# NHD-C12832A-Breakout.net
KiCad netlist of a schematic drawn in EAGLE
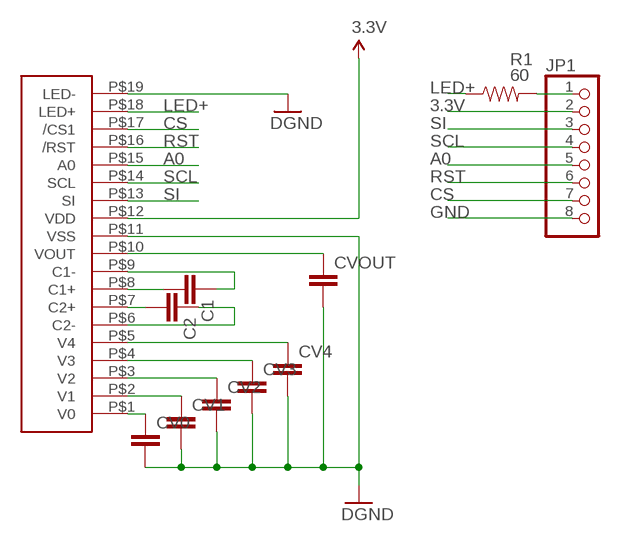
[diagram p0: schematic, sheet 1]

(export (version "E")
  (design (tool "Eeschema 10.0.6"))
  (components
    (comp (ref "C1")
      (value "C-EUC0805")
      (footprint "eagle-import:C0805")
      (libsource (lib "eagle-import") (part "C-EUC0805"))
    )
    (comp (ref "C2")
      (value "C-EUC0805")
      (footprint "eagle-import:C0805")
      (libsource (lib "eagle-import") (part "C-EUC0805"))
    )
    (comp (ref "CV0")
      (value "C-EUC0805")
      (footprint "eagle-import:C0805")
      (libsource (lib "eagle-import") (part "C-EUC0805"))
    )
    (comp (ref "CV1")
      (value "C-EUC0805")
      (footprint "eagle-import:C0805")
      (libsource (lib "eagle-import") (part "C-EUC0805"))
    )
    (comp (ref "CV2")
      (value "C-EUC0805")
      (footprint "eagle-import:C0805")
      (libsource (lib "eagle-import") (part "C-EUC0805"))
    )
    (comp (ref "CV3")
      (value "C-EUC0805")
      (footprint "eagle-import:C0805")
      (libsource (lib "eagle-import") (part "C-EUC0805"))
    )
    (comp (ref "CV4")
      (value "C-EUC0805")
      (footprint "eagle-import:C0805")
      (libsource (lib "eagle-import") (part "C-EUC0805"))
    )
    (comp (ref "CVOUT")
      (value "C-EUC0805")
      (footprint "eagle-import:C0805")
      (libsource (lib "eagle-import") (part "C-EUC0805"))
    )
    (comp (ref "JP1")
      (value "PINHD-1X8")
      (footprint "eagle-import:1X08")
      (libsource (lib "eagle-import") (part "PINHD-1X8"))
    )
    (comp (ref "R1")
      (value "60")
      (footprint "eagle-import:0805")
      (libsource (lib "eagle-import") (part "RESISTOR0805-RES"))
    )
    (comp (ref "U$1")
      (value "NHD-C12832A")
      (footprint "eagle-import:NHD-C12832A-PACK")
      (libsource (lib "eagle-import") (part "NHD-C12832A"))
    )
  )
  (nets
    (net (code "1") (name "/A0") (class "Default")
      (node (ref "JP1") (pin "5") (pinfunction "5_5") (pintype "passive"))
      (node (ref "U$1") (pin "P$15") (pinfunction "A0_P$15") (pintype "bidirectional"))
    )
    (net (code "2") (name "/CS") (class "Default")
      (node (ref "JP1") (pin "7") (pinfunction "7_7") (pintype "passive"))
      (node (ref "U$1") (pin "P$17") (pinfunction "/CS1_P$17") (pintype "bidirectional"))
    )
    (net (code "3") (name "/LED+") (class "Default")
      (node (ref "R1") (pin "1") (pinfunction "1_1") (pintype "passive"))
      (node (ref "U$1") (pin "P$18") (pinfunction "LED+_P$18") (pintype "bidirectional"))
    )
    (net (code "4") (name "/RST") (class "Default")
      (node (ref "JP1") (pin "6") (pinfunction "6_6") (pintype "passive"))
      (node (ref "U$1") (pin "P$16") (pinfunction "/RST_P$16") (pintype "bidirectional"))
    )
    (net (code "5") (name "/SCL") (class "Default")
      (node (ref "JP1") (pin "4") (pinfunction "4_4") (pintype "passive"))
      (node (ref "U$1") (pin "P$14") (pinfunction "SCL_P$14") (pintype "bidirectional"))
    )
    (net (code "6") (name "/SI") (class "Default")
      (node (ref "JP1") (pin "3") (pinfunction "3_3") (pintype "passive"))
      (node (ref "U$1") (pin "P$13") (pinfunction "SI_P$13") (pintype "bidirectional"))
    )
    (net (code "7") (name "3.3V") (class "Default")
      (node (ref "JP1") (pin "2") (pinfunction "2_2") (pintype "passive"))
      (node (ref "U$1") (pin "P$12") (pinfunction "VDD_P$12") (pintype "bidirectional"))
    )
    (net (code "8") (name "DGND") (class "Default")
      (node (ref "CV0") (pin "2") (pinfunction "2_2") (pintype "passive"))
      (node (ref "CV1") (pin "2") (pinfunction "2_2") (pintype "passive"))
      (node (ref "CV2") (pin "2") (pinfunction "2_2") (pintype "passive"))
      (node (ref "CV3") (pin "2") (pinfunction "2_2") (pintype "passive"))
      (node (ref "CV4") (pin "2") (pinfunction "2_2") (pintype "passive"))
      (node (ref "CVOUT") (pin "2") (pinfunction "2_2") (pintype "passive"))
      (node (ref "JP1") (pin "8") (pinfunction "8_8") (pintype "passive"))
      (node (ref "U$1") (pin "P$11") (pinfunction "VSS_P$11") (pintype "bidirectional"))
      (node (ref "U$1") (pin "P$19") (pinfunction "LED-_P$19") (pintype "bidirectional"))
    )
    (net (code "9") (name "Net-(JP1-Pad1)") (class "Default")
      (node (ref "JP1") (pin "1") (pinfunction "1_1") (pintype "passive"))
      (node (ref "R1") (pin "2") (pinfunction "2_2") (pintype "passive"))
    )
    (net (code "10") (name "Net-(U$1-C1+)") (class "Default")
      (node (ref "C1") (pin "2") (pinfunction "2_2") (pintype "passive"))
      (node (ref "U$1") (pin "P$8") (pinfunction "C1+_P$8") (pintype "bidirectional"))
    )
    (net (code "11") (name "Net-(U$1-C1-)") (class "Default")
      (node (ref "C1") (pin "1") (pinfunction "1_1") (pintype "passive"))
      (node (ref "U$1") (pin "P$9") (pinfunction "C1-_P$9") (pintype "bidirectional"))
    )
    (net (code "12") (name "Net-(U$1-C2+)") (class "Default")
      (node (ref "C2") (pin "2") (pinfunction "2_2") (pintype "passive"))
      (node (ref "U$1") (pin "P$7") (pinfunction "C2+_P$7") (pintype "bidirectional"))
    )
    (net (code "13") (name "Net-(U$1-C2-)") (class "Default")
      (node (ref "C2") (pin "1") (pinfunction "1_1") (pintype "passive"))
      (node (ref "U$1") (pin "P$6") (pinfunction "C2-_P$6") (pintype "bidirectional"))
    )
    (net (code "14") (name "Net-(U$1-V0)") (class "Default")
      (node (ref "CV0") (pin "1") (pinfunction "1_1") (pintype "passive"))
      (node (ref "U$1") (pin "P$1") (pinfunction "V0_P$1") (pintype "bidirectional"))
    )
    (net (code "15") (name "Net-(U$1-V1)") (class "Default")
      (node (ref "CV1") (pin "1") (pinfunction "1_1") (pintype "passive"))
      (node (ref "U$1") (pin "P$2") (pinfunction "V1_P$2") (pintype "bidirectional"))
    )
    (net (code "16") (name "Net-(U$1-V2)") (class "Default")
      (node (ref "CV2") (pin "1") (pinfunction "1_1") (pintype "passive"))
      (node (ref "U$1") (pin "P$3") (pinfunction "V2_P$3") (pintype "bidirectional"))
    )
    (net (code "17") (name "Net-(U$1-V3)") (class "Default")
      (node (ref "CV3") (pin "1") (pinfunction "1_1") (pintype "passive"))
      (node (ref "U$1") (pin "P$4") (pinfunction "V3_P$4") (pintype "bidirectional"))
    )
    (net (code "18") (name "Net-(U$1-V4)") (class "Default")
      (node (ref "CV4") (pin "1") (pinfunction "1_1") (pintype "passive"))
      (node (ref "U$1") (pin "P$5") (pinfunction "V4_P$5") (pintype "bidirectional"))
    )
    (net (code "19") (name "Net-(U$1-VOUT)") (class "Default")
      (node (ref "CVOUT") (pin "1") (pinfunction "1_1") (pintype "passive"))
      (node (ref "U$1") (pin "P$10") (pinfunction "VOUT_P$10") (pintype "bidirectional"))
    )
  )
)
